# draft3_4lyr-autoroute.net
KiCad netlist of a schematic drawn in EAGLE
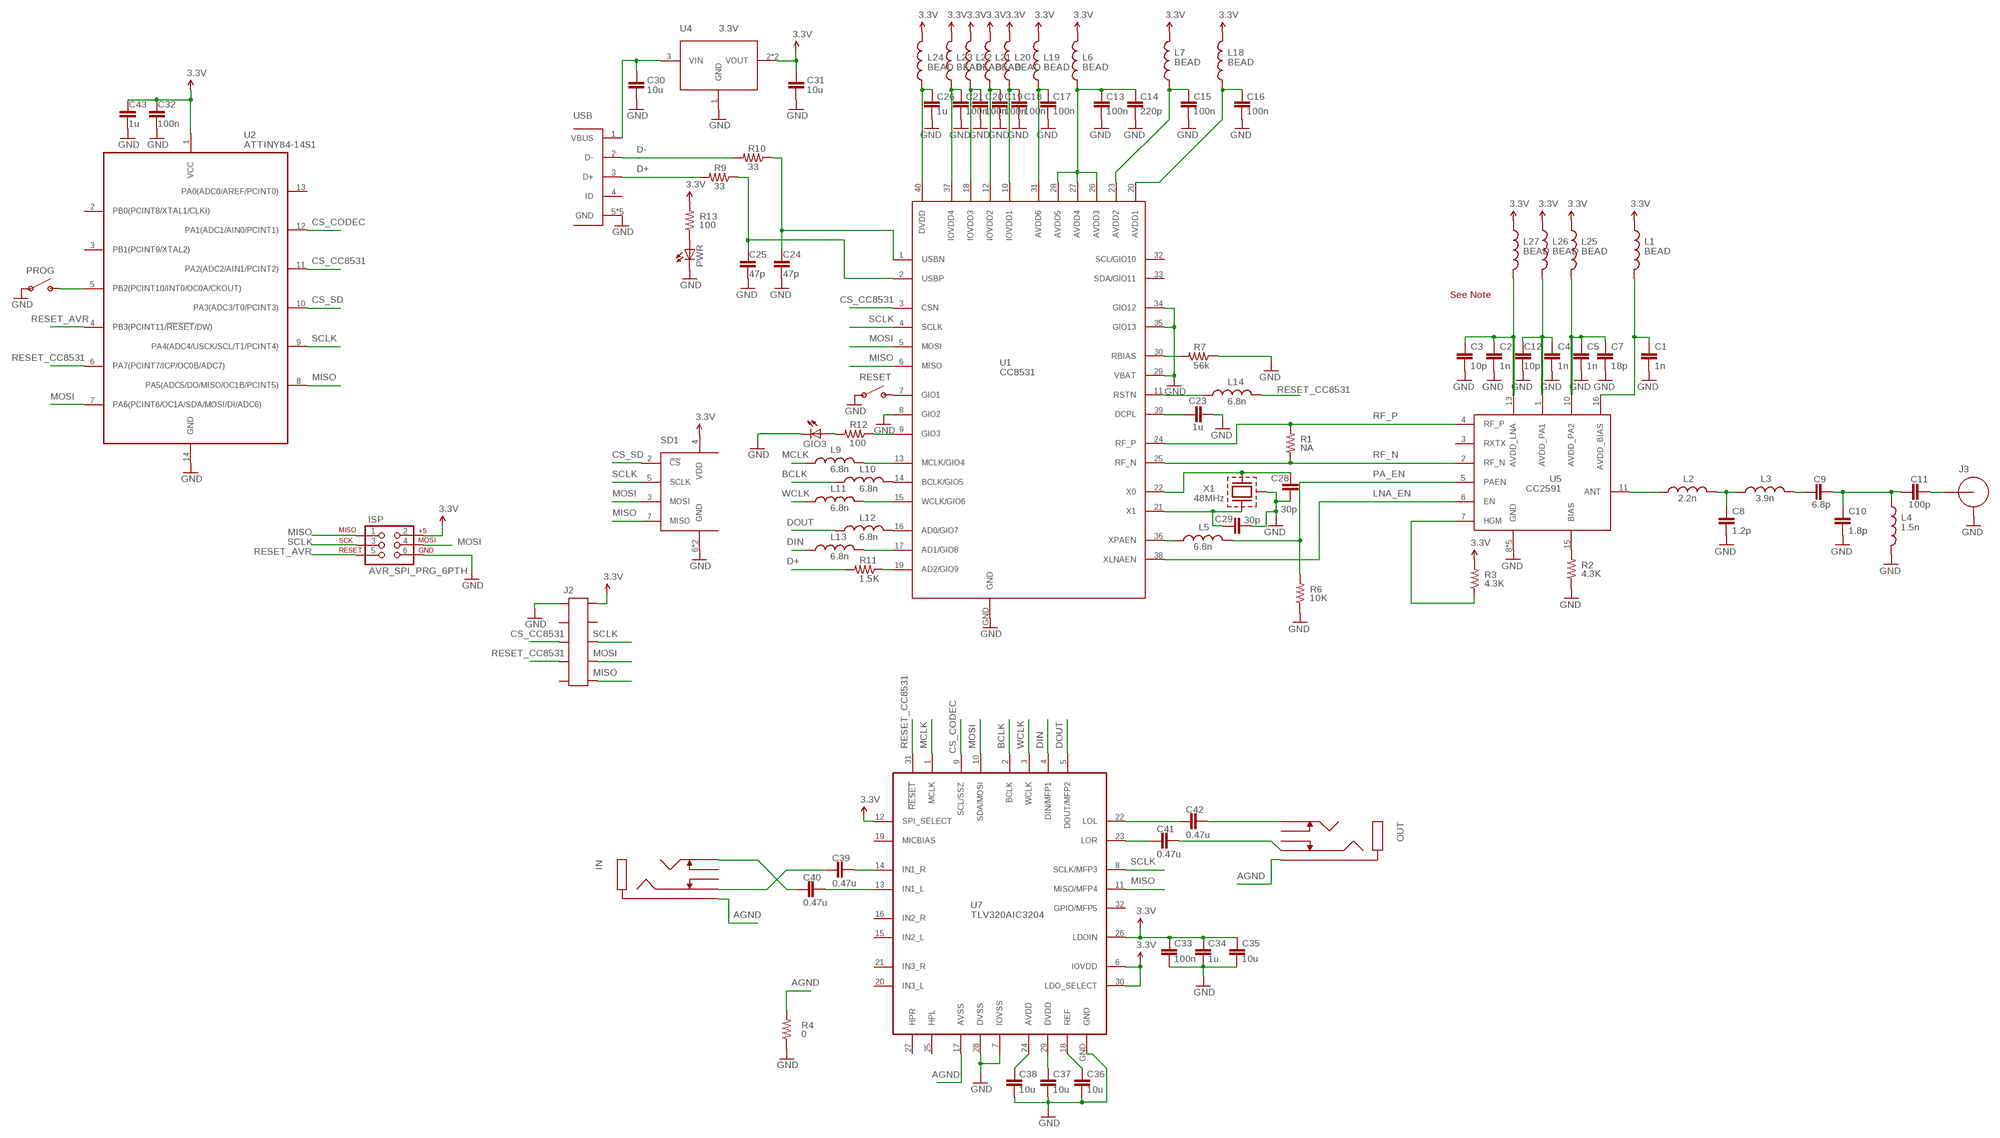
[diagram p0: schematic, sheet 1]

(export (version "E")
  (design (tool "Eeschema 10.0.6"))
  (components
    (comp (ref "C1")
      (value "1n")
      (footprint "eagle-import:C0603")
      (libsource (lib "eagle-import") (part "C-EUC0603"))
    )
    (comp (ref "C2")
      (value "1n")
      (footprint "eagle-import:C0603")
      (libsource (lib "eagle-import") (part "C-EUC0603"))
    )
    (comp (ref "C3")
      (value "10p")
      (footprint "eagle-import:C0603")
      (libsource (lib "eagle-import") (part "C-EUC0603"))
    )
    (comp (ref "C4")
      (value "1n")
      (footprint "eagle-import:C0603")
      (libsource (lib "eagle-import") (part "C-EUC0603"))
    )
    (comp (ref "C5")
      (value "1n")
      (footprint "eagle-import:C0603")
      (libsource (lib "eagle-import") (part "C-EUC0603"))
    )
    (comp (ref "C7")
      (value "18p")
      (footprint "eagle-import:C0603")
      (libsource (lib "eagle-import") (part "C-EUC0603"))
    )
    (comp (ref "C8")
      (value "1.2p")
      (footprint "eagle-import:C0603")
      (libsource (lib "eagle-import") (part "C-EUC0603"))
    )
    (comp (ref "C9")
      (value "6.8p")
      (footprint "eagle-import:C0603")
      (libsource (lib "eagle-import") (part "C-EUC0603"))
    )
    (comp (ref "C10")
      (value "1.8p")
      (footprint "eagle-import:C0603")
      (libsource (lib "eagle-import") (part "C-EUC0603"))
    )
    (comp (ref "C11")
      (value "100p")
      (footprint "eagle-import:C0603")
      (libsource (lib "eagle-import") (part "C-EUC0603"))
    )
    (comp (ref "C12")
      (value "10p")
      (footprint "eagle-import:C0603")
      (libsource (lib "eagle-import") (part "C-EUC0603"))
    )
    (comp (ref "C13")
      (value "100n")
      (footprint "eagle-import:C0603")
      (libsource (lib "eagle-import") (part "C-EUC0603"))
    )
    (comp (ref "C14")
      (value "220p")
      (footprint "eagle-import:C0603")
      (libsource (lib "eagle-import") (part "C-EUC0603"))
    )
    (comp (ref "C15")
      (value "100n")
      (footprint "eagle-import:C0603")
      (libsource (lib "eagle-import") (part "C-EUC0603"))
    )
    (comp (ref "C16")
      (value "100n")
      (footprint "eagle-import:C0603")
      (libsource (lib "eagle-import") (part "C-EUC0603"))
    )
    (comp (ref "C17")
      (value "100n")
      (footprint "eagle-import:C0603")
      (libsource (lib "eagle-import") (part "C-EUC0603"))
    )
    (comp (ref "C18")
      (value "100n")
      (footprint "eagle-import:C0603")
      (libsource (lib "eagle-import") (part "C-EUC0603"))
    )
    (comp (ref "C19")
      (value "100n")
      (footprint "eagle-import:C0603")
      (libsource (lib "eagle-import") (part "C-EUC0603"))
    )
    (comp (ref "C20")
      (value "100n")
      (footprint "eagle-import:C0603")
      (libsource (lib "eagle-import") (part "C-EUC0603"))
    )
    (comp (ref "C21")
      (value "100n")
      (footprint "eagle-import:C0603")
      (libsource (lib "eagle-import") (part "C-EUC0603"))
    )
    (comp (ref "C23")
      (value "1u")
      (footprint "eagle-import:C0603")
      (libsource (lib "eagle-import") (part "C-EUC0603"))
    )
    (comp (ref "C24")
      (value "47p")
      (footprint "eagle-import:C0603")
      (libsource (lib "eagle-import") (part "C-EUC0603"))
    )
    (comp (ref "C25")
      (value "47p")
      (footprint "eagle-import:C0603")
      (libsource (lib "eagle-import") (part "C-EUC0603"))
    )
    (comp (ref "C26")
      (value "1u")
      (footprint "eagle-import:C0603")
      (libsource (lib "eagle-import") (part "C-EUC0603"))
    )
    (comp (ref "C28")
      (value "30p")
      (footprint "eagle-import:C0603")
      (libsource (lib "eagle-import") (part "C-EUC0603"))
    )
    (comp (ref "C29")
      (value "30p")
      (footprint "eagle-import:C0603")
      (libsource (lib "eagle-import") (part "C-EUC0603"))
    )
    (comp (ref "C30")
      (value "10u")
      (footprint "eagle-import:C0603")
      (libsource (lib "eagle-import") (part "C-EUC0603"))
    )
    (comp (ref "C31")
      (value "10u")
      (footprint "eagle-import:C0603")
      (libsource (lib "eagle-import") (part "C-EUC0603"))
    )
    (comp (ref "C32")
      (value "100n")
      (footprint "eagle-import:C0603")
      (libsource (lib "eagle-import") (part "C-EUC0603"))
    )
    (comp (ref "C33")
      (value "100n")
      (footprint "eagle-import:C0603")
      (libsource (lib "eagle-import") (part "C-EUC0603"))
    )
    (comp (ref "C34")
      (value "1u")
      (footprint "eagle-import:C0603")
      (libsource (lib "eagle-import") (part "C-EUC0603"))
    )
    (comp (ref "C35")
      (value "10u")
      (footprint "eagle-import:C0603")
      (libsource (lib "eagle-import") (part "C-EUC0603"))
    )
    (comp (ref "C36")
      (value "10u")
      (footprint "eagle-import:C0603")
      (libsource (lib "eagle-import") (part "C-EUC0603"))
    )
    (comp (ref "C37")
      (value "10u")
      (footprint "eagle-import:C0603")
      (libsource (lib "eagle-import") (part "C-EUC0603"))
    )
    (comp (ref "C38")
      (value "10u")
      (footprint "eagle-import:C0603")
      (libsource (lib "eagle-import") (part "C-EUC0603"))
    )
    (comp (ref "C39")
      (value "0.47u")
      (footprint "eagle-import:C0603")
      (libsource (lib "eagle-import") (part "C-EUC0603"))
    )
    (comp (ref "C40")
      (value "0.47u")
      (footprint "eagle-import:C0603")
      (libsource (lib "eagle-import") (part "C-EUC0603"))
    )
    (comp (ref "C41")
      (value "0.47u")
      (footprint "eagle-import:C0603")
      (libsource (lib "eagle-import") (part "C-EUC0603"))
    )
    (comp (ref "C42")
      (value "0.47u")
      (footprint "eagle-import:C0603")
      (libsource (lib "eagle-import") (part "C-EUC0603"))
    )
    (comp (ref "C43")
      (value "1u")
      (footprint "eagle-import:C0603")
      (libsource (lib "eagle-import") (part "C-EUC0603"))
    )
    (comp (ref "GIO3")
      (value "LEDCHIP-LED0603")
      (footprint "eagle-import:CHIP-LED0603")
      (libsource (lib "eagle-import") (part "LEDCHIP-LED0603"))
    )
    (comp (ref "IN")
      (value "PHONE_SW")
      (footprint "eagle-import:35RAPC4BV4")
      (libsource (lib "eagle-import") (part "PHONE_SW"))
    )
    (comp (ref "ISP")
      (value "AVR_SPI_PRG_6PTH")
      (footprint "eagle-import:2X3")
      (libsource (lib "eagle-import") (part "AVR_SPI_PRG_6PTH"))
    )
    (comp (ref "J2")
      (value "HEADER-10P-SMD-MALE")
      (footprint "eagle-import:10P-0.05-HEADER")
      (libsource (lib "eagle-import") (part "HEADER-10P-SMD-MALE"))
    )
    (comp (ref "J3")
      (value "SMA")
      (footprint "eagle-import:CONSMA003.031")
      (libsource (lib "eagle-import") (part "SMA"))
    )
    (comp (ref "L1")
      (value "BEAD")
      (footprint "eagle-import:0603")
      (libsource (lib "eagle-import") (part "INDUCTOR0603"))
    )
    (comp (ref "L2")
      (value "2.2n")
      (footprint "eagle-import:0603")
      (libsource (lib "eagle-import") (part "INDUCTOR0603"))
    )
    (comp (ref "L3")
      (value "3.9n")
      (footprint "eagle-import:0603")
      (libsource (lib "eagle-import") (part "INDUCTOR0603"))
    )
    (comp (ref "L4")
      (value "1.5n")
      (footprint "eagle-import:0603")
      (libsource (lib "eagle-import") (part "INDUCTOR0603"))
    )
    (comp (ref "L5")
      (value "6.8n")
      (footprint "eagle-import:0603")
      (libsource (lib "eagle-import") (part "INDUCTOR0603"))
    )
    (comp (ref "L6")
      (value "BEAD")
      (footprint "eagle-import:0603")
      (libsource (lib "eagle-import") (part "INDUCTOR0603"))
    )
    (comp (ref "L7")
      (value "BEAD")
      (footprint "eagle-import:0603")
      (libsource (lib "eagle-import") (part "INDUCTOR0603"))
    )
    (comp (ref "L9")
      (value "6.8n")
      (footprint "eagle-import:0603")
      (libsource (lib "eagle-import") (part "INDUCTOR0603"))
    )
    (comp (ref "L10")
      (value "6.8n")
      (footprint "eagle-import:0603")
      (libsource (lib "eagle-import") (part "INDUCTOR0603"))
    )
    (comp (ref "L11")
      (value "6.8n")
      (footprint "eagle-import:0603")
      (libsource (lib "eagle-import") (part "INDUCTOR0603"))
    )
    (comp (ref "L12")
      (value "6.8n")
      (footprint "eagle-import:0603")
      (libsource (lib "eagle-import") (part "INDUCTOR0603"))
    )
    (comp (ref "L13")
      (value "6.8n")
      (footprint "eagle-import:0603")
      (libsource (lib "eagle-import") (part "INDUCTOR0603"))
    )
    (comp (ref "L14")
      (value "6.8n")
      (footprint "eagle-import:0603")
      (libsource (lib "eagle-import") (part "INDUCTOR0603"))
    )
    (comp (ref "L18")
      (value "BEAD")
      (footprint "eagle-import:0603")
      (libsource (lib "eagle-import") (part "INDUCTOR0603"))
    )
    (comp (ref "L19")
      (value "BEAD")
      (footprint "eagle-import:0603")
      (libsource (lib "eagle-import") (part "INDUCTOR0603"))
    )
    (comp (ref "L20")
      (value "BEAD")
      (footprint "eagle-import:0603")
      (libsource (lib "eagle-import") (part "INDUCTOR0603"))
    )
    (comp (ref "L21")
      (value "BEAD")
      (footprint "eagle-import:0603")
      (libsource (lib "eagle-import") (part "INDUCTOR0603"))
    )
    (comp (ref "L22")
      (value "BEAD")
      (footprint "eagle-import:0603")
      (libsource (lib "eagle-import") (part "INDUCTOR0603"))
    )
    (comp (ref "L23")
      (value "BEAD")
      (footprint "eagle-import:0603")
      (libsource (lib "eagle-import") (part "INDUCTOR0603"))
    )
    (comp (ref "L24")
      (value "BEAD")
      (footprint "eagle-import:0603")
      (libsource (lib "eagle-import") (part "INDUCTOR0603"))
    )
    (comp (ref "L25")
      (value "BEAD")
      (footprint "eagle-import:0603")
      (libsource (lib "eagle-import") (part "INDUCTOR0603"))
    )
    (comp (ref "L26")
      (value "BEAD")
      (footprint "eagle-import:0603")
      (libsource (lib "eagle-import") (part "INDUCTOR0603"))
    )
    (comp (ref "L27")
      (value "BEAD")
      (footprint "eagle-import:0603")
      (libsource (lib "eagle-import") (part "INDUCTOR0603"))
    )
    (comp (ref "OUT")
      (value "PHONE_SW")
      (footprint "eagle-import:35RAPC4BV4")
      (libsource (lib "eagle-import") (part "PHONE_SW"))
    )
    (comp (ref "PROG")
      (value "SPST-SMD")
      (footprint "eagle-import:TACT_SW")
      (libsource (lib "eagle-import") (part "SPST-SMD"))
    )
    (comp (ref "PWR")
      (value "LEDCHIP-LED0603")
      (footprint "eagle-import:CHIP-LED0603")
      (libsource (lib "eagle-import") (part "LEDCHIP-LED0603"))
    )
    (comp (ref "R1")
      (value "NA")
      (footprint "eagle-import:R0603")
      (libsource (lib "eagle-import") (part "R-US_R0603"))
    )
    (comp (ref "R2")
      (value "4.3K")
      (footprint "eagle-import:R0603")
      (libsource (lib "eagle-import") (part "R-US_R0603"))
    )
    (comp (ref "R3")
      (value "4.3K")
      (footprint "eagle-import:R0603")
      (libsource (lib "eagle-import") (part "R-US_R0603"))
    )
    (comp (ref "R4")
      (value "0")
      (footprint "eagle-import:R0603")
      (libsource (lib "eagle-import") (part "R-US_R0603"))
    )
    (comp (ref "R6")
      (value "10K")
      (footprint "eagle-import:R0603")
      (libsource (lib "eagle-import") (part "R-US_R0603"))
    )
    (comp (ref "R7")
      (value "56k")
      (footprint "eagle-import:R0603")
      (libsource (lib "eagle-import") (part "R-US_R0603"))
    )
    (comp (ref "R9")
      (value "33")
      (footprint "eagle-import:R0603")
      (libsource (lib "eagle-import") (part "R-US_R0603"))
    )
    (comp (ref "R10")
      (value "33")
      (footprint "eagle-import:R0603")
      (libsource (lib "eagle-import") (part "R-US_R0603"))
    )
    (comp (ref "R11")
      (value "1.5K")
      (footprint "eagle-import:R0603")
      (libsource (lib "eagle-import") (part "R-US_R0603"))
    )
    (comp (ref "R12")
      (value "100")
      (footprint "eagle-import:R0603")
      (libsource (lib "eagle-import") (part "R-US_R0603"))
    )
    (comp (ref "R13")
      (value "100")
      (footprint "eagle-import:R0603")
      (libsource (lib "eagle-import") (part "R-US_R0603"))
    )
    (comp (ref "RESET")
      (value "SPST-SMD")
      (footprint "eagle-import:TACT_SW")
      (libsource (lib "eagle-import") (part "SPST-SMD"))
    )
    (comp (ref "SD1")
      (value "MICROSDDM3AT")
      (footprint "eagle-import:DM3AT")
      (libsource (lib "eagle-import") (part "MICROSDDM3AT"))
    )
    (comp (ref "U1")
      (value "CC8531")
      (footprint "eagle-import:S-PVQFN-N40")
      (libsource (lib "eagle-import") (part "CC8531"))
    )
    (comp (ref "U2")
      (value "ATTINY84-14S1")
      (footprint "eagle-import:SOIC14")
      (libsource (lib "eagle-import") (part "ATTINY84-14S1"))
    )
    (comp (ref "U4")
      (value "3.3V")
      (footprint "eagle-import:SOT-223")
      (libsource (lib "eagle-import") (part "NX1117C"))
    )
    (comp (ref "U5")
      (value "CC2591")
      (footprint "eagle-import:S-PVQFN-N16")
      (libsource (lib "eagle-import") (part "CC2591"))
    )
    (comp (ref "U7")
      (value "TLV320AIC3204")
      (footprint "eagle-import:S-PVQFN-N32")
      (libsource (lib "eagle-import") (part "TLV320AIC3204"))
    )
    (comp (ref "USB")
      (value "USB_MICRO_AB")
      (footprint "eagle-import:USB_MICRO_AB")
      (libsource (lib "eagle-import") (part "USB_MICRO_AB"))
    )
    (comp (ref "X1")
      (value "48MHz")
      (footprint "eagle-import:ABM3C")
      (libsource (lib "eagle-import") (part "XTAL-ABRACONABM3C"))
    )
  )
  (nets
    (net (code "1") (name "/AGND") (class "Default")
      (node (ref "IN") (pin "1") (pinfunction "GND_1") (pintype "bidirectional"))
      (node (ref "OUT") (pin "1") (pinfunction "GND_1") (pintype "bidirectional"))
      (node (ref "R4") (pin "2") (pinfunction "2_2") (pintype "passive"))
      (node (ref "U7") (pin "17") (pinfunction "AVSS_17") (pintype "bidirectional"))
    )
    (net (code "2") (name "/BCLK") (class "Default")
      (node (ref "L10") (pin "1") (pinfunction "1_1") (pintype "passive"))
      (node (ref "U7") (pin "2") (pinfunction "BCLK_2") (pintype "bidirectional"))
    )
    (net (code "3") (name "/CS_CC8531") (class "Default")
      (node (ref "J2") (pin "5") (pinfunction "5_5") (pintype "bidirectional"))
      (node (ref "U1") (pin "3") (pinfunction "CSN_3") (pintype "bidirectional"))
      (node (ref "U2") (pin "11") (pinfunction "PA2(ADC2/AIN1/PCINT2)_11") (pintype "bidirectional"))
    )
    (net (code "4") (name "/CS_CODEC") (class "Default")
      (node (ref "U2") (pin "12") (pinfunction "PA1(ADC1/AIN0/PCINT1)_12") (pintype "bidirectional"))
      (node (ref "U7") (pin "9") (pinfunction "SCL/SSZ_9") (pintype "bidirectional"))
    )
    (net (code "5") (name "/CS_SD") (class "Default")
      (node (ref "SD1") (pin "2") (pinfunction "~{CS}_2") (pintype "bidirectional"))
      (node (ref "U2") (pin "10") (pinfunction "PA3(ADC3/T0/PCINT3)_10") (pintype "bidirectional"))
    )
    (net (code "6") (name "/D+") (class "Default")
      (node (ref "R11") (pin "2") (pinfunction "2_2") (pintype "passive"))
      (node (ref "R9") (pin "2") (pinfunction "2_2") (pintype "passive"))
      (node (ref "USB") (pin "3") (pinfunction "D+_3") (pintype "bidirectional"))
    )
    (net (code "7") (name "/D-") (class "Default")
      (node (ref "R10") (pin "2") (pinfunction "2_2") (pintype "passive"))
      (node (ref "USB") (pin "2") (pinfunction "D-_2") (pintype "bidirectional"))
    )
    (net (code "8") (name "/DIN") (class "Default")
      (node (ref "L13") (pin "1") (pinfunction "1_1") (pintype "passive"))
      (node (ref "U7") (pin "4") (pinfunction "DIN/MFP1_4") (pintype "bidirectional"))
    )
    (net (code "9") (name "/DOUT") (class "Default")
      (node (ref "L12") (pin "1") (pinfunction "1_1") (pintype "passive"))
      (node (ref "U7") (pin "5") (pinfunction "DOUT/MFP2_5") (pintype "bidirectional"))
    )
    (net (code "10") (name "/LNA_EN") (class "Default")
      (node (ref "U1") (pin "38") (pinfunction "XLNAEN_38") (pintype "bidirectional"))
      (node (ref "U5") (pin "6") (pinfunction "EN_6") (pintype "bidirectional"))
    )
    (net (code "11") (name "/MCLK") (class "Default")
      (node (ref "L9") (pin "1") (pinfunction "1_1") (pintype "passive"))
      (node (ref "U7") (pin "1") (pinfunction "MCLK_1") (pintype "bidirectional"))
    )
    (net (code "12") (name "/MISO") (class "Default")
      (node (ref "ISP") (pin "1") (pinfunction "1_1") (pintype "passive"))
      (node (ref "J2") (pin "10") (pinfunction "10_10") (pintype "bidirectional"))
      (node (ref "SD1") (pin "7") (pinfunction "MISO_7") (pintype "bidirectional"))
      (node (ref "U1") (pin "6") (pinfunction "MISO_6") (pintype "bidirectional"))
      (node (ref "U2") (pin "8") (pinfunction "PA5(ADC5/DO/MISO/OC1B/PCINT5)_8") (pintype "bidirectional"))
      (node (ref "U7") (pin "11") (pinfunction "MISO/MFP4_11") (pintype "bidirectional"))
    )
    (net (code "13") (name "/MOSI") (class "Default")
      (node (ref "ISP") (pin "4") (pinfunction "4_4") (pintype "passive"))
      (node (ref "J2") (pin "8") (pinfunction "8_8") (pintype "bidirectional"))
      (node (ref "SD1") (pin "3") (pinfunction "MOSI_3") (pintype "bidirectional"))
      (node (ref "U1") (pin "5") (pinfunction "MOSI_5") (pintype "bidirectional"))
      (node (ref "U2") (pin "7") (pinfunction "PA6(PCINT6/OC1A/SDA/MOSI/DI/ADC6)_7") (pintype "bidirectional"))
      (node (ref "U7") (pin "10") (pinfunction "SDA/MOSI_10") (pintype "bidirectional"))
    )
    (net (code "14") (name "/PA_EN") (class "Default")
      (node (ref "L5") (pin "2") (pinfunction "2_2") (pintype "passive"))
      (node (ref "R6") (pin "2") (pinfunction "2_2") (pintype "passive"))
      (node (ref "U5") (pin "5") (pinfunction "PAEN_5") (pintype "bidirectional"))
    )
    (net (code "15") (name "/RESET_AVR") (class "Default")
      (node (ref "ISP") (pin "5") (pinfunction "5_5") (pintype "passive"))
      (node (ref "U2") (pin "4") (pinfunction "PB3(PCINT11/~{RESET}/DW)_4") (pintype "bidirectional"))
    )
    (net (code "16") (name "/RESET_CC8531") (class "Default")
      (node (ref "J2") (pin "7") (pinfunction "7_7") (pintype "bidirectional"))
      (node (ref "L14") (pin "2") (pinfunction "2_2") (pintype "passive"))
      (node (ref "U2") (pin "6") (pinfunction "PA7(PCINT7/ICP/OC0B/ADC7)_6") (pintype "bidirectional"))
      (node (ref "U7") (pin "31") (pinfunction "~{RESET}_31") (pintype "bidirectional"))
    )
    (net (code "17") (name "/RF_N") (class "Default")
      (node (ref "R1") (pin "1") (pinfunction "1_1") (pintype "passive"))
      (node (ref "U1") (pin "25") (pinfunction "RF_N_25") (pintype "bidirectional"))
      (node (ref "U5") (pin "2") (pinfunction "RF_N_2") (pintype "bidirectional"))
    )
    (net (code "18") (name "/RF_P") (class "Default")
      (node (ref "R1") (pin "2") (pinfunction "2_2") (pintype "passive"))
      (node (ref "U1") (pin "24") (pinfunction "RF_P_24") (pintype "bidirectional"))
      (node (ref "U5") (pin "4") (pinfunction "RF_P_4") (pintype "bidirectional"))
    )
    (net (code "19") (name "/SCLK") (class "Default")
      (node (ref "ISP") (pin "3") (pinfunction "3_3") (pintype "passive"))
      (node (ref "J2") (pin "6") (pinfunction "6_6") (pintype "bidirectional"))
      (node (ref "SD1") (pin "5") (pinfunction "SCLK_5") (pintype "bidirectional"))
      (node (ref "U1") (pin "4") (pinfunction "SCLK_4") (pintype "bidirectional"))
      (node (ref "U2") (pin "9") (pinfunction "PA4(ADC4/USCK/SCL/T1/PCINT4)_9") (pintype "bidirectional"))
      (node (ref "U7") (pin "8") (pinfunction "SCLK/MFP3_8") (pintype "bidirectional"))
    )
    (net (code "20") (name "/WCLK") (class "Default")
      (node (ref "L11") (pin "1") (pinfunction "1_1") (pintype "passive"))
      (node (ref "U7") (pin "3") (pinfunction "WCLK_3") (pintype "bidirectional"))
    )
    (net (code "21") (name "3.3V") (class "Default")
      (node (ref "C31") (pin "1") (pinfunction "1_1") (pintype "passive"))
      (node (ref "C32") (pin "1") (pinfunction "1_1") (pintype "passive"))
      (node (ref "C33") (pin "1") (pinfunction "1_1") (pintype "passive"))
      (node (ref "C34") (pin "1") (pinfunction "1_1") (pintype "passive"))
      (node (ref "C35") (pin "1") (pinfunction "1_1") (pintype "passive"))
      (node (ref "C43") (pin "1") (pinfunction "1_1") (pintype "passive"))
      (node (ref "ISP") (pin "2") (pinfunction "2_2") (pintype "passive"))
      (node (ref "J2") (pin "2") (pinfunction "2_2") (pintype "bidirectional"))
      (node (ref "L1") (pin "1") (pinfunction "1_1") (pintype "passive"))
      (node (ref "L18") (pin "2") (pinfunction "2_2") (pintype "passive"))
      (node (ref "L19") (pin "2") (pinfunction "2_2") (pintype "passive"))
      (node (ref "L20") (pin "2") (pinfunction "2_2") (pintype "passive"))
      (node (ref "L21") (pin "2") (pinfunction "2_2") (pintype "passive"))
      (node (ref "L22") (pin "2") (pinfunction "2_2") (pintype "passive"))
      (node (ref "L23") (pin "2") (pinfunction "2_2") (pintype "passive"))
      (node (ref "L24") (pin "2") (pinfunction "2_2") (pintype "passive"))
      (node (ref "L25") (pin "1") (pinfunction "1_1") (pintype "passive"))
      (node (ref "L26") (pin "1") (pinfunction "1_1") (pintype "passive"))
      (node (ref "L27") (pin "1") (pinfunction "1_1") (pintype "passive"))
      (node (ref "L6") (pin "2") (pinfunction "2_2") (pintype "passive"))
      (node (ref "L7") (pin "2") (pinfunction "2_2") (pintype "passive"))
      (node (ref "R13") (pin "2") (pinfunction "2_2") (pintype "passive"))
      (node (ref "R3") (pin "2") (pinfunction "2_2") (pintype "passive"))
      (node (ref "SD1") (pin "4") (pinfunction "VDD_4") (pintype "bidirectional"))
      (node (ref "U2") (pin "1") (pinfunction "VCC_1") (pintype "bidirectional"))
      (node (ref "U4") (pin "2") (pinfunction "VOUT_2") (pintype "bidirectional"))
      (node (ref "U4") (pin "4") (pinfunction "VOUT_4") (pintype "bidirectional"))
      (node (ref "U7") (pin "12") (pinfunction "SPI_SELECT_12") (pintype "bidirectional"))
      (node (ref "U7") (pin "26") (pinfunction "LDOIN_26") (pintype "bidirectional"))
      (node (ref "U7") (pin "30") (pinfunction "LDO_SELECT_30") (pintype "bidirectional"))
      (node (ref "U7") (pin "6") (pinfunction "IOVDD_6") (pintype "bidirectional"))
    )
    (net (code "22") (name "GND") (class "Default")
      (node (ref "C1") (pin "2") (pinfunction "2_2") (pintype "passive"))
      (node (ref "C10") (pin "2") (pinfunction "2_2") (pintype "passive"))
      (node (ref "C12") (pin "2") (pinfunction "2_2") (pintype "passive"))
      (node (ref "C13") (pin "2") (pinfunction "2_2") (pintype "passive"))
      (node (ref "C14") (pin "2") (pinfunction "2_2") (pintype "passive"))
      (node (ref "C15") (pin "2") (pinfunction "2_2") (pintype "passive"))
      (node (ref "C16") (pin "2") (pinfunction "2_2") (pintype "passive"))
      (node (ref "C17") (pin "2") (pinfunction "2_2") (pintype "passive"))
      (node (ref "C18") (pin "2") (pinfunction "2_2") (pintype "passive"))
      (node (ref "C19") (pin "2") (pinfunction "2_2") (pintype "passive"))
      (node (ref "C2") (pin "2") (pinfunction "2_2") (pintype "passive"))
      (node (ref "C20") (pin "2") (pinfunction "2_2") (pintype "passive"))
      (node (ref "C21") (pin "2") (pinfunction "2_2") (pintype "passive"))
      (node (ref "C23") (pin "2") (pinfunction "2_2") (pintype "passive"))
      (node (ref "C24") (pin "2") (pinfunction "2_2") (pintype "passive"))
      (node (ref "C25") (pin "2") (pinfunction "2_2") (pintype "passive"))
      (node (ref "C26") (pin "2") (pinfunction "2_2") (pintype "passive"))
      (node (ref "C28") (pin "2") (pinfunction "2_2") (pintype "passive"))
      (node (ref "C29") (pin "2") (pinfunction "2_2") (pintype "passive"))
      (node (ref "C3") (pin "2") (pinfunction "2_2") (pintype "passive"))
      (node (ref "C30") (pin "2") (pinfunction "2_2") (pintype "passive"))
      (node (ref "C31") (pin "2") (pinfunction "2_2") (pintype "passive"))
      (node (ref "C32") (pin "2") (pinfunction "2_2") (pintype "passive"))
      (node (ref "C33") (pin "2") (pinfunction "2_2") (pintype "passive"))
      (node (ref "C34") (pin "2") (pinfunction "2_2") (pintype "passive"))
      (node (ref "C35") (pin "2") (pinfunction "2_2") (pintype "passive"))
      (node (ref "C36") (pin "2") (pinfunction "2_2") (pintype "passive"))
      (node (ref "C37") (pin "2") (pinfunction "2_2") (pintype "passive"))
      (node (ref "C38") (pin "2") (pinfunction "2_2") (pintype "passive"))
      (node (ref "C4") (pin "2") (pinfunction "2_2") (pintype "passive"))
      (node (ref "C43") (pin "2") (pinfunction "2_2") (pintype "passive"))
      (node (ref "C5") (pin "2") (pinfunction "2_2") (pintype "passive"))
      (node (ref "C7") (pin "2") (pinfunction "2_2") (pintype "passive"))
      (node (ref "C8") (pin "2") (pinfunction "2_2") (pintype "passive"))
      (node (ref "GIO3") (pin "C") (pinfunction "C_C") (pintype "passive"))
      (node (ref "ISP") (pin "6") (pinfunction "6_6") (pintype "passive"))
      (node (ref "J2") (pin "1") (pinfunction "1_1") (pintype "bidirectional"))
      (node (ref "J3") (pin "GND1") (pinfunction "GND_GND1") (pintype "bidirectional"))
      (node (ref "J3") (pin "GND2") (pinfunction "GND_GND2") (pintype "bidirectional"))
      (node (ref "J3") (pin "GND3") (pinfunction "GND_GND3") (pintype "bidirectional"))
      (node (ref "J3") (pin "GND4") (pinfunction "GND_GND4") (pintype "bidirectional"))
      (node (ref "L4") (pin "2") (pinfunction "2_2") (pintype "passive"))
      (node (ref "PROG") (pin "1") (pinfunction "P$1_1") (pintype "bidirectional"))
      (node (ref "PROG") (pin "2") (pinfunction "P$1_2") (pintype "bidirectional"))
      (node (ref "PWR") (pin "C") (pinfunction "C_C") (pintype "passive"))
      (node (ref "R2") (pin "1") (pinfunction "1_1") (pintype "passive"))
      (node (ref "R4") (pin "1") (pinfunction "1_1") (pintype "passive"))
      (node (ref "R6") (pin "1") (pinfunction "1_1") (pintype "passive"))
      (node (ref "R7") (pin "1") (pinfunction "1_1") (pintype "passive"))
      (node (ref "RESET") (pin "1") (pinfunction "P$1_1") (pintype "bidirectional"))
      (node (ref "RESET") (pin "2") (pinfunction "P$1_2") (pintype "bidirectional"))
      (node (ref "SD1") (pin "6") (pinfunction "GND_6") (pintype "bidirectional"))
      (node (ref "SD1") (pin "GND") (pinfunction "GND_GND") (pintype "bidirectional"))
      (node (ref "U1") (pin "29") (pinfunction "VBAT_29") (pintype "bidirectional"))
      (node (ref "U1") (pin "34") (pinfunction "GIO12_34") (pintype "bidirectional"))
      (node (ref "U1") (pin "35") (pinfunction "GIO13_35") (pintype "bidirectional"))
      (node (ref "U1") (pin "8") (pinfunction "GIO2_8") (pintype "bidirectional"))
      (node (ref "U1") (pin "GND") (pinfunction "GND_GND") (pintype "bidirectional"))
      (node (ref "U2") (pin "14") (pinfunction "GND_14") (pintype "bidirectional"))
      (node (ref "U4") (pin "1") (pinfunction "GND_1") (pintype "bidirectional"))
      (node (ref "U5") (pin "12") (pinfunction "GND_12") (pintype "bidirectional"))
      (node (ref "U5") (pin "14") (pinfunction "GND_14") (pintype "bidirectional"))
      (node (ref "U5") (pin "8") (pinfunction "GND_8") (pintype "bidirectional"))
      (node (ref "U5") (pin "9") (pinfunction "GND_9") (pintype "bidirectional"))
      (node (ref "U5") (pin "GND") (pinfunction "GND_GND") (pintype "bidirectional"))
      (node (ref "U7") (pin "28") (pinfunction "DVSS_28") (pintype "bidirectional"))
      (node (ref "U7") (pin "7") (pinfunction "IOVSS_7") (pintype "bidirectional"))
      (node (ref "U7") (pin "GND") (pinfunction "GND_GND") (pintype "bidirectional"))
      (node (ref "USB") (pin "5") (pinfunction "GND_5") (pintype "bidirectional"))
      (node (ref "USB") (pin "GND1") (pinfunction "GND_GND1") (pintype "bidirectional"))
      (node (ref "USB") (pin "GND2") (pinfunction "GND_GND2") (pintype "bidirectional"))
      (node (ref "USB") (pin "GND3") (pinfunction "GND_GND3") (pintype "bidirectional"))
      (node (ref "USB") (pin "GND4") (pinfunction "GND_GND4") (pintype "bidirectional"))
      (node (ref "X1") (pin "2") (pinfunction "CASE_2") (pintype "passive"))
      (node (ref "X1") (pin "4") (pinfunction "CASE_4") (pintype "passive"))
    )
    (net (code "23") (name "Net-(C8-Pad1)") (class "Default")
      (node (ref "C8") (pin "1") (pinfunction "1_1") (pintype "passive"))
      (node (ref "L2") (pin "2") (pinfunction "2_2") (pintype "passive"))
      (node (ref "L3") (pin "1") (pinfunction "1_1") (pintype "passive"))
    )
    (net (code "24") (name "Net-(C9-Pad1)") (class "Default")
      (node (ref "C9") (pin "1") (pinfunction "1_1") (pintype "passive"))
      (node (ref "L3") (pin "2") (pinfunction "2_2") (pintype "passive"))
    )
    (net (code "25") (name "Net-(C10-Pad1)") (class "Default")
      (node (ref "C10") (pin "1") (pinfunction "1_1") (pintype "passive"))
      (node (ref "C11") (pin "1") (pinfunction "1_1") (pintype "passive"))
      (node (ref "C9") (pin "2") (pinfunction "2_2") (pintype "passive"))
      (node (ref "L4") (pin "1") (pinfunction "1_1") (pintype "passive"))
    )
    (net (code "26") (name "Net-(C11-Pad2)") (class "Default")
      (node (ref "C11") (pin "2") (pinfunction "2_2") (pintype "passive"))
      (node (ref "J3") (pin "SIG") (pinfunction "SIG_SIG") (pintype "bidirectional"))
    )
    (net (code "27") (name "Net-(GIO3-PadA)") (class "Default")
      (node (ref "GIO3") (pin "A") (pinfunction "A_A") (pintype "passive"))
      (node (ref "R12") (pin "2") (pinfunction "2_2") (pintype "passive"))
    )
    (net (code "28") (name "Net-(IN-L)") (class "Default")
      (node (ref "C40") (pin "1") (pinfunction "1_1") (pintype "passive"))
      (node (ref "IN") (pin "2") (pinfunction "L_2") (pintype "bidirectional"))
    )
    (net (code "29") (name "Net-(IN-R)") (class "Default")
      (node (ref "C39") (pin "1") (pinfunction "1_1") (pintype "passive"))
      (node (ref "IN") (pin "4") (pinfunction "R_4") (pintype "bidirectional"))
    )
    (net (code "30") (name "Net-(OUT-L)") (class "Default")
      (node (ref "C42") (pin "2") (pinfunction "2_2") (pintype "passive"))
      (node (ref "OUT") (pin "2") (pinfunction "L_2") (pintype "bidirectional"))
    )
    (net (code "31") (name "Net-(OUT-R)") (class "Default")
      (node (ref "C41") (pin "2") (pinfunction "2_2") (pintype "passive"))
      (node (ref "OUT") (pin "4") (pinfunction "R_4") (pintype "bidirectional"))
    )
    (net (code "32") (name "Net-(PWR-PadA)") (class "Default")
      (node (ref "PWR") (pin "A") (pinfunction "A_A") (pintype "passive"))
      (node (ref "R13") (pin "1") (pinfunction "1_1") (pintype "passive"))
    )
    (net (code "33") (name "Net-(U1-AD0{slash}GIO7)") (class "Default")
      (node (ref "L12") (pin "2") (pinfunction "2_2") (pintype "passive"))
      (node (ref "U1") (pin "16") (pinfunction "AD0/GIO7_16") (pintype "bidirectional"))
    )
    (net (code "34") (name "Net-(U1-AD1{slash}GIO8)") (class "Default")
      (node (ref "L13") (pin "2") (pinfunction "2_2") (pintype "passive"))
      (node (ref "U1") (pin "17") (pinfunction "AD1/GIO8_17") (pintype "bidirectional"))
    )
    (net (code "35") (name "Net-(U1-AD2{slash}GIO9)") (class "Default")
      (node (ref "R11") (pin "1") (pinfunction "1_1") (pintype "passive"))
      (node (ref "U1") (pin "19") (pinfunction "AD2/GIO9_19") (pintype "bidirectional"))
    )
    (net (code "36") (name "Net-(U1-AVDD1)") (class "Default")
      (node (ref "C16") (pin "1") (pinfunction "1_1") (pintype "passive"))
      (node (ref "L18") (pin "1") (pinfunction "1_1") (pintype "passive"))
      (node (ref "U1") (pin "20") (pinfunction "AVDD1_20") (pintype "bidirectional"))
    )
    (net (code "37") (name "Net-(U1-AVDD2)") (class "Default")
      (node (ref "C15") (pin "1") (pinfunction "1_1") (pintype "passive"))
      (node (ref "L7") (pin "1") (pinfunction "1_1") (pintype "passive"))
      (node (ref "U1") (pin "23") (pinfunction "AVDD2_23") (pintype "bidirectional"))
    )
    (net (code "38") (name "Net-(U1-AVDD3)") (class "Default")
      (node (ref "C13") (pin "1") (pinfunction "1_1") (pintype "passive"))
      (node (ref "C14") (pin "1") (pinfunction "1_1") (pintype "passive"))
      (node (ref "L6") (pin "1") (pinfunction "1_1") (pintype "passive"))
      (node (ref "U1") (pin "26") (pinfunction "AVDD3_26") (pintype "bidirectional"))
      (node (ref "U1") (pin "27") (pinfunction "AVDD4_27") (pintype "bidirectional"))
      (node (ref "U1") (pin "28") (pinfunction "AVDD5_28") (pintype "bidirectional"))
    )
    (net (code "39") (name "Net-(U1-AVDD6)") (class "Default")
      (node (ref "C17") (pin "1") (pinfunction "1_1") (pintype "passive"))
      (node (ref "L19") (pin "1") (pinfunction "1_1") (pintype "passive"))
      (node (ref "U1") (pin "31") (pinfunction "AVDD6_31") (pintype "bidirectional"))
    )
    (net (code "40") (name "Net-(U1-BCLK{slash}GIO5)") (class "Default")
      (node (ref "L10") (pin "2") (pinfunction "2_2") (pintype "passive"))
      (node (ref "U1") (pin "14") (pinfunction "BCLK/GIO5_14") (pintype "bidirectional"))
    )
    (net (code "41") (name "Net-(U1-DCPL)") (class "Default")
      (node (ref "C23") (pin "1") (pinfunction "1_1") (pintype "passive"))
      (node (ref "U1") (pin "39") (pinfunction "DCPL_39") (pintype "bidirectional"))
    )
    (net (code "42") (name "Net-(U1-DVDD)") (class "Default")
      (node (ref "C26") (pin "1") (pinfunction "1_1") (pintype "passive"))
      (node (ref "L24") (pin "1") (pinfunction "1_1") (pintype "passive"))
      (node (ref "U1") (pin "40") (pinfunction "DVDD_40") (pintype "bidirectional"))
    )
    (net (code "43") (name "Net-(U1-GIO1)") (class "Default")
      (node (ref "RESET") (pin "3") (pinfunction "P$2_3") (pintype "bidirectional"))
      (node (ref "RESET") (pin "4") (pinfunction "P$2_4") (pintype "bidirectional"))
      (node (ref "U1") (pin "7") (pinfunction "GIO1_7") (pintype "bidirectional"))
    )
    (net (code "44") (name "Net-(U1-GIO3)") (class "Default")
      (node (ref "R12") (pin "1") (pinfunction "1_1") (pintype "passive"))
      (node (ref "U1") (pin "9") (pinfunction "GIO3_9") (pintype "bidirectional"))
    )
    (net (code "45") (name "Net-(U1-IOVDD1)") (class "Default")
      (node (ref "C18") (pin "1") (pinfunction "1_1") (pintype "passive"))
      (node (ref "L20") (pin "1") (pinfunction "1_1") (pintype "passive"))
      (node (ref "U1") (pin "10") (pinfunction "IOVDD1_10") (pintype "bidirectional"))
    )
    (net (code "46") (name "Net-(U1-IOVDD2)") (class "Default")
      (node (ref "C19") (pin "1") (pinfunction "1_1") (pintype "passive"))
      (node (ref "L21") (pin "1") (pinfunction "1_1") (pintype "passive"))
      (node (ref "U1") (pin "12") (pinfunction "IOVDD2_12") (pintype "bidirectional"))
    )
    (net (code "47") (name "Net-(U1-IOVDD3)") (class "Default")
      (node (ref "C20") (pin "1") (pinfunction "1_1") (pintype "passive"))
      (node (ref "L22") (pin "1") (pinfunction "1_1") (pintype "passive"))
      (node (ref "U1") (pin "18") (pinfunction "IOVDD3_18") (pintype "bidirectional"))
    )
    (net (code "48") (name "Net-(U1-IOVDD4)") (class "Default")
      (node (ref "C21") (pin "1") (pinfunction "1_1") (pintype "passive"))
      (node (ref "L23") (pin "1") (pinfunction "1_1") (pintype "passive"))
      (node (ref "U1") (pin "37") (pinfunction "IOVDD4_37") (pintype "bidirectional"))
    )
    (net (code "49") (name "Net-(U1-MCLK{slash}GIO4)") (class "Default")
      (node (ref "L9") (pin "2") (pinfunction "2_2") (pintype "passive"))
      (node (ref "U1") (pin "13") (pinfunction "MCLK/GIO4_13") (pintype "bidirectional"))
    )
    (net (code "50") (name "Net-(U1-RBIAS)") (class "Default")
      (node (ref "R7") (pin "2") (pinfunction "2_2") (pintype "passive"))
      (node (ref "U1") (pin "30") (pinfunction "RBIAS_30") (pintype "bidirectional"))
    )
    (net (code "51") (name "Net-(U1-RSTN)") (class "Default")
      (node (ref "L14") (pin "1") (pinfunction "1_1") (pintype "passive"))
      (node (ref "U1") (pin "11") (pinfunction "RSTN_11") (pintype "bidirectional"))
    )
    (net (code "52") (name "Net-(U1-USBN)") (class "Default")
      (node (ref "C24") (pin "1") (pinfunction "1_1") (pintype "passive"))
      (node (ref "R10") (pin "1") (pinfunction "1_1") (pintype "passive"))
      (node (ref "U1") (pin "1") (pinfunction "USBN_1") (pintype "bidirectional"))
    )
    (net (code "53") (name "Net-(U1-USBP)") (class "Default")
      (node (ref "C25") (pin "1") (pinfunction "1_1") (pintype "passive"))
      (node (ref "R9") (pin "1") (pinfunction "1_1") (pintype "passive"))
      (node (ref "U1") (pin "2") (pinfunction "USBP_2") (pintype "bidirectional"))
    )
    (net (code "54") (name "Net-(U1-WCLK{slash}GIO6)") (class "Default")
      (node (ref "L11") (pin "2") (pinfunction "2_2") (pintype "passive"))
      (node (ref "U1") (pin "15") (pinfunction "WCLK/GIO6_15") (pintype "bidirectional"))
    )
    (net (code "55") (name "Net-(U1-X0)") (class "Default")
      (node (ref "C28") (pin "1") (pinfunction "1_1") (pintype "passive"))
      (node (ref "U1") (pin "22") (pinfunction "X0_22") (pintype "bidirectional"))
      (node (ref "X1") (pin "3") (pinfunction "2_3") (pintype "passive"))
    )
    (net (code "56") (name "Net-(U1-X1)") (class "Default")
      (node (ref "C29") (pin "1") (pinfunction "1_1") (pintype "passive"))
      (node (ref "U1") (pin "21") (pinfunction "X1_21") (pintype "bidirectional"))
      (node (ref "X1") (pin "1") (pinfunction "1_1") (pintype "passive"))
    )
    (net (code "57") (name "Net-(U1-XPAEN)") (class "Default")
      (node (ref "L5") (pin "1") (pinfunction "1_1") (pintype "passive"))
      (node (ref "U1") (pin "36") (pinfunction "XPAEN_36") (pintype "bidirectional"))
    )
    (net (code "58") (name "Net-(U2-PB2(PCINT10{slash}INT0{slash}OC0A{slash}CKOUT))") (class "Default")
      (node (ref "PROG") (pin "3") (pinfunction "P$2_3") (pintype "bidirectional"))
      (node (ref "PROG") (pin "4") (pinfunction "P$2_4") (pintype "bidirectional"))
      (node (ref "U2") (pin "5") (pinfunction "PB2(PCINT10/INT0/OC0A/CKOUT)_5") (pintype "bidirectional"))
    )
    (net (code "59") (name "Net-(U4-VIN)") (class "Default")
      (node (ref "C30") (pin "1") (pinfunction "1_1") (pintype "passive"))
      (node (ref "U4") (pin "3") (pinfunction "VIN_3") (pintype "bidirectional"))
      (node (ref "USB") (pin "1") (pinfunction "VBUS_1") (pintype "bidirectional"))
    )
    (net (code "60") (name "Net-(U5-ANT)") (class "Default")
      (node (ref "L2") (pin "1") (pinfunction "1_1") (pintype "passive"))
      (node (ref "U5") (pin "11") (pinfunction "ANT_11") (pintype "bidirectional"))
    )
    (net (code "61") (name "Net-(U5-AVDD_BIAS)") (class "Default")
      (node (ref "C1") (pin "1") (pinfunction "1_1") (pintype "passive"))
      (node (ref "L1") (pin "2") (pinfunction "2_2") (pintype "passive"))
      (node (ref "U5") (pin "16") (pinfunction "AVDD_BIAS_16") (pintype "bidirectional"))
    )
    (net (code "62") (name "Net-(U5-AVDD_LNA)") (class "Default")
      (node (ref "C2") (pin "1") (pinfunction "1_1") (pintype "passive"))
      (node (ref "C3") (pin "1") (pinfunction "1_1") (pintype "passive"))
      (node (ref "L27") (pin "2") (pinfunction "2_2") (pintype "passive"))
      (node (ref "U5") (pin "13") (pinfunction "AVDD_LNA_13") (pintype "bidirectional"))
    )
    (net (code "63") (name "Net-(U5-AVDD_PA1)") (class "Default")
      (node (ref "C12") (pin "1") (pinfunction "1_1") (pintype "passive"))
      (node (ref "C4") (pin "1") (pinfunction "1_1") (pintype "passive"))
      (node (ref "L26") (pin "2") (pinfunction "2_2") (pintype "passive"))
      (node (ref "U5") (pin "1") (pinfunction "AVDD_PA1_1") (pintype "bidirectional"))
    )
    (net (code "64") (name "Net-(U5-AVDD_PA2)") (class "Default")
      (node (ref "C5") (pin "1") (pinfunction "1_1") (pintype "passive"))
      (node (ref "C7") (pin "1") (pinfunction "1_1") (pintype "passive"))
      (node (ref "L25") (pin "2") (pinfunction "2_2") (pintype "passive"))
      (node (ref "U5") (pin "10") (pinfunction "AVDD_PA2_10") (pintype "bidirectional"))
    )
    (net (code "65") (name "Net-(U5-BIAS)") (class "Default")
      (node (ref "R2") (pin "2") (pinfunction "2_2") (pintype "passive"))
      (node (ref "U5") (pin "15") (pinfunction "BIAS_15") (pintype "bidirectional"))
    )
    (net (code "66") (name "Net-(U5-HGM)") (class "Default")
      (node (ref "R3") (pin "1") (pinfunction "1_1") (pintype "passive"))
      (node (ref "U5") (pin "7") (pinfunction "HGM_7") (pintype "bidirectional"))
    )
    (net (code "67") (name "Net-(U7-AVDD)") (class "Default")
      (node (ref "C38") (pin "1") (pinfunction "1_1") (pintype "passive"))
      (node (ref "U7") (pin "24") (pinfunction "AVDD_24") (pintype "bidirectional"))
    )
    (net (code "68") (name "Net-(U7-DVDD)") (class "Default")
      (node (ref "C37") (pin "1") (pinfunction "1_1") (pintype "passive"))
      (node (ref "U7") (pin "29") (pinfunction "DVDD_29") (pintype "bidirectional"))
    )
    (net (code "69") (name "Net-(U7-IN1_L)") (class "Default")
      (node (ref "C40") (pin "2") (pinfunction "2_2") (pintype "passive"))
      (node (ref "U7") (pin "13") (pinfunction "IN1_L_13") (pintype "bidirectional"))
    )
    (net (code "70") (name "Net-(U7-IN1_R)") (class "Default")
      (node (ref "C39") (pin "2") (pinfunction "2_2") (pintype "passive"))
      (node (ref "U7") (pin "14") (pinfunction "IN1_R_14") (pintype "bidirectional"))
    )
    (net (code "71") (name "Net-(U7-LOL)") (class "Default")
      (node (ref "C42") (pin "1") (pinfunction "1_1") (pintype "passive"))
      (node (ref "U7") (pin "22") (pinfunction "LOL_22") (pintype "bidirectional"))
    )
    (net (code "72") (name "Net-(U7-LOR)") (class "Default")
      (node (ref "C41") (pin "1") (pinfunction "1_1") (pintype "passive"))
      (node (ref "U7") (pin "23") (pinfunction "LOR_23") (pintype "bidirectional"))
    )
    (net (code "73") (name "Net-(U7-REF)") (class "Default")
      (node (ref "C36") (pin "1") (pinfunction "1_1") (pintype "passive"))
      (node (ref "U7") (pin "18") (pinfunction "REF_18") (pintype "bidirectional"))
    )
    (net (code "74") (name "unconnected-(IN-L_SW-Pad5)") (class "Default")
      (node (ref "IN") (pin "5") (pinfunction "L_SW_5") (pintype "bidirectional"))
    )
    (net (code "75") (name "unconnected-(IN-R_SW-Pad3)") (class "Default")
      (node (ref "IN") (pin "3") (pinfunction "R_SW_3") (pintype "bidirectional"))
    )
    (net (code "76") (name "unconnected-(J2-Pad3)") (class "Default")
      (node (ref "J2") (pin "3") (pinfunction "3_3") (pintype "bidirectional"))
    )
    (net (code "77") (name "unconnected-(J2-Pad4)") (class "Default")
      (node (ref "J2") (pin "4") (pinfunction "4_4") (pintype "bidirectional"))
    )
    (net (code "78") (name "unconnected-(J2-Pad9)") (class "Default")
      (node (ref "J2") (pin "9") (pinfunction "9_9") (pintype "bidirectional"))
    )
    (net (code "79") (name "unconnected-(OUT-L_SW-Pad5)") (class "Default")
      (node (ref "OUT") (pin "5") (pinfunction "L_SW_5") (pintype "bidirectional"))
    )
    (net (code "80") (name "unconnected-(OUT-R_SW-Pad3)") (class "Default")
      (node (ref "OUT") (pin "3") (pinfunction "R_SW_3") (pintype "bidirectional"))
    )
    (net (code "81") (name "unconnected-(U1-SCL{slash}GIO10-Pad32)") (class "Default")
      (node (ref "U1") (pin "32") (pinfunction "SCL/GIO10_32") (pintype "bidirectional"))
    )
    (net (code "82") (name "unconnected-(U1-SDA{slash}GIO11-Pad33)") (class "Default")
      (node (ref "U1") (pin "33") (pinfunction "SDA/GIO11_33") (pintype "bidirectional"))
    )
    (net (code "83") (name "unconnected-(U2-PA0(ADC0{slash}AREF{slash}PCINT0)-Pad13)") (class "Default")
      (node (ref "U2") (pin "13") (pinfunction "PA0(ADC0/AREF/PCINT0)_13") (pintype "bidirectional"))
    )
    (net (code "84") (name "unconnected-(U2-PB0(PCINT8{slash}XTAL1{slash}CLKI)-Pad2)") (class "Default")
      (node (ref "U2") (pin "2") (pinfunction "PB0(PCINT8/XTAL1/CLKI)_2") (pintype "bidirectional"))
    )
    (net (code "85") (name "unconnected-(U2-PB1(PCINT9{slash}XTAL2)-Pad3)") (class "Default")
      (node (ref "U2") (pin "3") (pinfunction "PB1(PCINT9/XTAL2)_3") (pintype "bidirectional"))
    )
    (net (code "86") (name "unconnected-(U5-RXTX-Pad3)") (class "Default")
      (node (ref "U5") (pin "3") (pinfunction "RXTX_3") (pintype "bidirectional"))
    )
    (net (code "87") (name "unconnected-(U7-GPIO{slash}MFP5-Pad32)") (class "Default")
      (node (ref "U7") (pin "32") (pinfunction "GPIO/MFP5_32") (pintype "bidirectional"))
    )
    (net (code "88") (name "unconnected-(U7-HPL-Pad25)") (class "Default")
      (node (ref "U7") (pin "25") (pinfunction "HPL_25") (pintype "bidirectional"))
    )
    (net (code "89") (name "unconnected-(U7-HPR-Pad27)") (class "Default")
      (node (ref "U7") (pin "27") (pinfunction "HPR_27") (pintype "bidirectional"))
    )
    (net (code "90") (name "unconnected-(U7-IN2_L-Pad15)") (class "Default")
      (node (ref "U7") (pin "15") (pinfunction "IN2_L_15") (pintype "bidirectional"))
    )
    (net (code "91") (name "unconnected-(U7-IN2_R-Pad16)") (class "Default")
      (node (ref "U7") (pin "16") (pinfunction "IN2_R_16") (pintype "bidirectional"))
    )
    (net (code "92") (name "unconnected-(U7-IN3_L-Pad20)") (class "Default")
      (node (ref "U7") (pin "20") (pinfunction "IN3_L_20") (pintype "bidirectional"))
    )
    (net (code "93") (name "unconnected-(U7-IN3_R-Pad21)") (class "Default")
      (node (ref "U7") (pin "21") (pinfunction "IN3_R_21") (pintype "bidirectional"))
    )
    (net (code "94") (name "unconnected-(U7-MICBIAS-Pad19)") (class "Default")
      (node (ref "U7") (pin "19") (pinfunction "MICBIAS_19") (pintype "bidirectional"))
    )
    (net (code "95") (name "unconnected-(USB-ID-Pad4)") (class "Default")
      (node (ref "USB") (pin "4") (pinfunction "ID_4") (pintype "bidirectional"))
    )
  )
)
